# Digital_Port_L_Button.net
KiCad netlist of a schematic drawn in Altium Designer
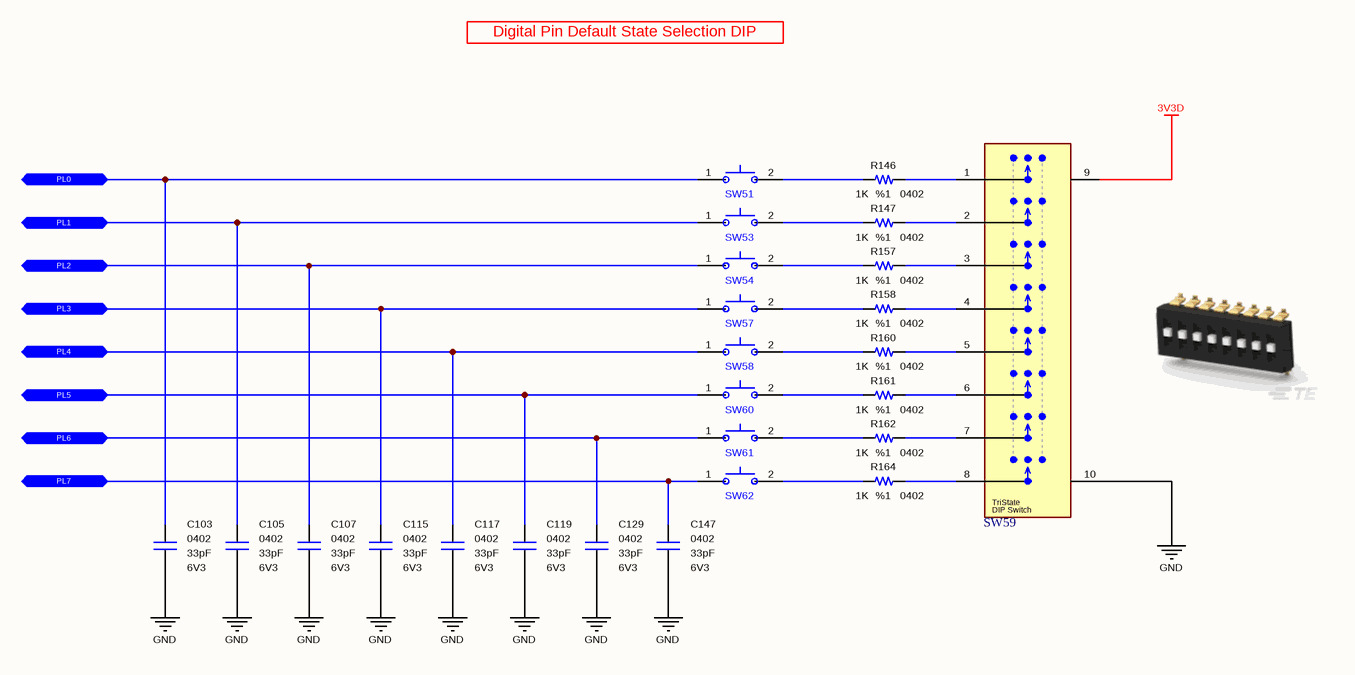
[diagram p0: Digital Port L Button.SchDoc]

(export (version "E")
  (design (tool "Eeschema 10.0.6"))
  (components
    (comp (ref "C103")
      (value "33pF")
      (footprint "CAPACITOR_0402")
      (description "Capacitor - 33pF [0402] (Ceramic)")
      (fields
        (field (name "MANUFACTURER PART NUMBER") "C0402C330J9RACAUTO")
        (field (name "MOUSER PART NUMBER") "80-C0402C330J9RAUTO")
        (field (name "CASE") "0402")
        (field (name "VOLTAGE") "6V3")
      )
      (libsource (lib "Ovoo_Library") (part "Capacitor - 33pF [0402-6V3]"))
    )
    (comp (ref "C105")
      (value "33pF")
      (footprint "CAPACITOR_0402")
      (description "Capacitor - 33pF [0402] (Ceramic)")
      (fields
        (field (name "MANUFACTURER PART NUMBER") "C0402C330J9RACAUTO")
        (field (name "MOUSER PART NUMBER") "80-C0402C330J9RAUTO")
        (field (name "CASE") "0402")
        (field (name "VOLTAGE") "6V3")
      )
      (libsource (lib "Ovoo_Library") (part "Capacitor - 33pF [0402-6V3]"))
    )
    (comp (ref "C107")
      (value "33pF")
      (footprint "CAPACITOR_0402")
      (description "Capacitor - 33pF [0402] (Ceramic)")
      (fields
        (field (name "MANUFACTURER PART NUMBER") "C0402C330J9RACAUTO")
        (field (name "MOUSER PART NUMBER") "80-C0402C330J9RAUTO")
        (field (name "CASE") "0402")
        (field (name "VOLTAGE") "6V3")
      )
      (libsource (lib "Ovoo_Library") (part "Capacitor - 33pF [0402-6V3]"))
    )
    (comp (ref "C115")
      (value "33pF")
      (footprint "CAPACITOR_0402")
      (description "Capacitor - 33pF [0402] (Ceramic)")
      (fields
        (field (name "MANUFACTURER PART NUMBER") "C0402C330J9RACAUTO")
        (field (name "MOUSER PART NUMBER") "80-C0402C330J9RAUTO")
        (field (name "CASE") "0402")
        (field (name "VOLTAGE") "6V3")
      )
      (libsource (lib "Ovoo_Library") (part "Capacitor - 33pF [0402-6V3]"))
    )
    (comp (ref "C117")
      (value "33pF")
      (footprint "CAPACITOR_0402")
      (description "Capacitor - 33pF [0402] (Ceramic)")
      (fields
        (field (name "MANUFACTURER PART NUMBER") "C0402C330J9RACAUTO")
        (field (name "MOUSER PART NUMBER") "80-C0402C330J9RAUTO")
        (field (name "CASE") "0402")
        (field (name "VOLTAGE") "6V3")
      )
      (libsource (lib "Ovoo_Library") (part "Capacitor - 33pF [0402-6V3]"))
    )
    (comp (ref "C119")
      (value "33pF")
      (footprint "CAPACITOR_0402")
      (description "Capacitor - 33pF [0402] (Ceramic)")
      (fields
        (field (name "MANUFACTURER PART NUMBER") "C0402C330J9RACAUTO")
        (field (name "MOUSER PART NUMBER") "80-C0402C330J9RAUTO")
        (field (name "CASE") "0402")
        (field (name "VOLTAGE") "6V3")
      )
      (libsource (lib "Ovoo_Library") (part "Capacitor - 33pF [0402-6V3]"))
    )
    (comp (ref "C129")
      (value "33pF")
      (footprint "CAPACITOR_0402")
      (description "Capacitor - 33pF [0402] (Ceramic)")
      (fields
        (field (name "MANUFACTURER PART NUMBER") "C0402C330J9RACAUTO")
        (field (name "MOUSER PART NUMBER") "80-C0402C330J9RAUTO")
        (field (name "CASE") "0402")
        (field (name "VOLTAGE") "6V3")
      )
      (libsource (lib "Ovoo_Library") (part "Capacitor - 33pF [0402-6V3]"))
    )
    (comp (ref "C147")
      (value "33pF")
      (footprint "CAPACITOR_0402")
      (description "Capacitor - 33pF [0402] (Ceramic)")
      (fields
        (field (name "MANUFACTURER PART NUMBER") "C0402C330J9RACAUTO")
        (field (name "MOUSER PART NUMBER") "80-C0402C330J9RAUTO")
        (field (name "CASE") "0402")
        (field (name "VOLTAGE") "6V3")
      )
      (libsource (lib "Ovoo_Library") (part "Capacitor - 33pF [0402-6V3]"))
    )
    (comp (ref "R146")
      (value "1K")
      (footprint "RESISTOR_0402")
      (description "Thick Film Resistors - SMD 1/16 W 1.0 Kohms 1%")
      (fields
        (field (name "MANUFACTURER PART NUMBER") "CRCW04021K00FKED")
        (field (name "MOUSER PART NUMBER") "71-CRCW0402-1.0K-E3")
        (field (name "TOLERANCE") "%1")
        (field (name "CASE") "0402")
      )
      (libsource (lib "Ovoo_Library") (part "Resistor - 1K"))
    )
    (comp (ref "R147")
      (value "1K")
      (footprint "RESISTOR_0402")
      (description "Thick Film Resistors - SMD 1/16 W 1.0 Kohms 1%")
      (fields
        (field (name "MANUFACTURER PART NUMBER") "CRCW04021K00FKED")
        (field (name "MOUSER PART NUMBER") "71-CRCW0402-1.0K-E3")
        (field (name "TOLERANCE") "%1")
        (field (name "CASE") "0402")
      )
      (libsource (lib "Ovoo_Library") (part "Resistor - 1K"))
    )
    (comp (ref "R157")
      (value "1K")
      (footprint "RESISTOR_0402")
      (description "Thick Film Resistors - SMD 1/16 W 1.0 Kohms 1%")
      (fields
        (field (name "MANUFACTURER PART NUMBER") "CRCW04021K00FKED")
        (field (name "MOUSER PART NUMBER") "71-CRCW0402-1.0K-E3")
        (field (name "TOLERANCE") "%1")
        (field (name "CASE") "0402")
      )
      (libsource (lib "Ovoo_Library") (part "Resistor - 1K"))
    )
    (comp (ref "R158")
      (value "1K")
      (footprint "RESISTOR_0402")
      (description "Thick Film Resistors - SMD 1/16 W 1.0 Kohms 1%")
      (fields
        (field (name "MANUFACTURER PART NUMBER") "CRCW04021K00FKED")
        (field (name "MOUSER PART NUMBER") "71-CRCW0402-1.0K-E3")
        (field (name "TOLERANCE") "%1")
        (field (name "CASE") "0402")
      )
      (libsource (lib "Ovoo_Library") (part "Resistor - 1K"))
    )
    (comp (ref "R160")
      (value "1K")
      (footprint "RESISTOR_0402")
      (description "Thick Film Resistors - SMD 1/16 W 1.0 Kohms 1%")
      (fields
        (field (name "MANUFACTURER PART NUMBER") "CRCW04021K00FKED")
        (field (name "MOUSER PART NUMBER") "71-CRCW0402-1.0K-E3")
        (field (name "TOLERANCE") "%1")
        (field (name "CASE") "0402")
      )
      (libsource (lib "Ovoo_Library") (part "Resistor - 1K"))
    )
    (comp (ref "R161")
      (value "1K")
      (footprint "RESISTOR_0402")
      (description "Thick Film Resistors - SMD 1/16 W 1.0 Kohms 1%")
      (fields
        (field (name "MANUFACTURER PART NUMBER") "CRCW04021K00FKED")
        (field (name "MOUSER PART NUMBER") "71-CRCW0402-1.0K-E3")
        (field (name "TOLERANCE") "%1")
        (field (name "CASE") "0402")
      )
      (libsource (lib "Ovoo_Library") (part "Resistor - 1K"))
    )
    (comp (ref "R162")
      (value "1K")
      (footprint "RESISTOR_0402")
      (description "Thick Film Resistors - SMD 1/16 W 1.0 Kohms 1%")
      (fields
        (field (name "MANUFACTURER PART NUMBER") "CRCW04021K00FKED")
        (field (name "MOUSER PART NUMBER") "71-CRCW0402-1.0K-E3")
        (field (name "TOLERANCE") "%1")
        (field (name "CASE") "0402")
      )
      (libsource (lib "Ovoo_Library") (part "Resistor - 1K"))
    )
    (comp (ref "R164")
      (value "1K")
      (footprint "RESISTOR_0402")
      (description "Thick Film Resistors - SMD 1/16 W 1.0 Kohms 1%")
      (fields
        (field (name "MANUFACTURER PART NUMBER") "CRCW04021K00FKED")
        (field (name "MOUSER PART NUMBER") "71-CRCW0402-1.0K-E3")
        (field (name "TOLERANCE") "%1")
        (field (name "CASE") "0402")
      )
      (libsource (lib "Ovoo_Library") (part "Resistor - 1K"))
    )
    (comp (ref "SW51")
      (value "Tactile Switches")
      (footprint "PTS526_Switch")
      (description "Tactile Switches 50mA 12VDC, 5.2x5.2mm, 0.8mm H, 260gf, G leads.")
      (fields
        (field (name "MANUFACTURER PART NUMBER") "PTS526 SK08 SMTR2 LFS")
        (field (name "MOUSER PART NUMBER") "611-PTS526SK08SMTR2L")
      )
      (libsource (lib "Ovoo_Library") (part "Switch - Tactile"))
    )
    (comp (ref "SW53")
      (value "Tactile Switches")
      (footprint "PTS526_Switch")
      (description "Tactile Switches 50mA 12VDC, 5.2x5.2mm, 0.8mm H, 260gf, G leads.")
      (fields
        (field (name "MANUFACTURER PART NUMBER") "PTS526 SK08 SMTR2 LFS")
        (field (name "MOUSER PART NUMBER") "611-PTS526SK08SMTR2L")
      )
      (libsource (lib "Ovoo_Library") (part "Switch - Tactile"))
    )
    (comp (ref "SW54")
      (value "Tactile Switches")
      (footprint "PTS526_Switch")
      (description "Tactile Switches 50mA 12VDC, 5.2x5.2mm, 0.8mm H, 260gf, G leads.")
      (fields
        (field (name "MANUFACTURER PART NUMBER") "PTS526 SK08 SMTR2 LFS")
        (field (name "MOUSER PART NUMBER") "611-PTS526SK08SMTR2L")
      )
      (libsource (lib "Ovoo_Library") (part "Switch - Tactile"))
    )
    (comp (ref "SW57")
      (value "Tactile Switches")
      (footprint "PTS526_Switch")
      (description "Tactile Switches 50mA 12VDC, 5.2x5.2mm, 0.8mm H, 260gf, G leads.")
      (fields
        (field (name "MANUFACTURER PART NUMBER") "PTS526 SK08 SMTR2 LFS")
        (field (name "MOUSER PART NUMBER") "611-PTS526SK08SMTR2L")
      )
      (libsource (lib "Ovoo_Library") (part "Switch - Tactile"))
    )
    (comp (ref "SW58")
      (value "Tactile Switches")
      (footprint "PTS526_Switch")
      (description "Tactile Switches 50mA 12VDC, 5.2x5.2mm, 0.8mm H, 260gf, G leads.")
      (fields
        (field (name "MANUFACTURER PART NUMBER") "PTS526 SK08 SMTR2 LFS")
        (field (name "MOUSER PART NUMBER") "611-PTS526SK08SMTR2L")
      )
      (libsource (lib "Ovoo_Library") (part "Switch - Tactile"))
    )
    (comp (ref "SW59")
      (value "DIP Switches/SIP Switches")
      (footprint "TDS08SGNNTR04")
      (description "DIP Switches/SIP Switches TRI-STATE DIP 8P G RAISED T&R")
      (fields
        (field (name "MANUFACTURER PART NUMBER") "TDS08SGNNTR04")
        (field (name "MOUSER PART NUMBER") "506-TDS08SGNNTR04")
      )
      (libsource (lib "Ovoo_Library") (part "Switch - DIP Switch (8 Pole TriState)"))
    )
    (comp (ref "SW60")
      (value "Tactile Switches")
      (footprint "PTS526_Switch")
      (description "Tactile Switches 50mA 12VDC, 5.2x5.2mm, 0.8mm H, 260gf, G leads.")
      (fields
        (field (name "MANUFACTURER PART NUMBER") "PTS526 SK08 SMTR2 LFS")
        (field (name "MOUSER PART NUMBER") "611-PTS526SK08SMTR2L")
      )
      (libsource (lib "Ovoo_Library") (part "Switch - Tactile"))
    )
    (comp (ref "SW61")
      (value "Tactile Switches")
      (footprint "PTS526_Switch")
      (description "Tactile Switches 50mA 12VDC, 5.2x5.2mm, 0.8mm H, 260gf, G leads.")
      (fields
        (field (name "MANUFACTURER PART NUMBER") "PTS526 SK08 SMTR2 LFS")
        (field (name "MOUSER PART NUMBER") "611-PTS526SK08SMTR2L")
      )
      (libsource (lib "Ovoo_Library") (part "Switch - Tactile"))
    )
    (comp (ref "SW62")
      (value "Tactile Switches")
      (footprint "PTS526_Switch")
      (description "Tactile Switches 50mA 12VDC, 5.2x5.2mm, 0.8mm H, 260gf, G leads.")
      (fields
        (field (name "MANUFACTURER PART NUMBER") "PTS526 SK08 SMTR2 LFS")
        (field (name "MOUSER PART NUMBER") "611-PTS526SK08SMTR2L")
      )
      (libsource (lib "Ovoo_Library") (part "Switch - Tactile"))
    )
  )
  (nets
    (net (code "1") (name "/PL0") (class "Default")
      (node (ref "C103") (pin "2") (pinfunction "2_2") (pintype "passive"))
      (node (ref "SW51") (pin "1") (pinfunction "NC_1") (pintype "passive"))
    )
    (net (code "2") (name "/PL1") (class "Default")
      (node (ref "C105") (pin "2") (pinfunction "2_2") (pintype "passive"))
      (node (ref "SW53") (pin "1") (pinfunction "NC_1") (pintype "passive"))
    )
    (net (code "3") (name "/PL2") (class "Default")
      (node (ref "C107") (pin "2") (pinfunction "2_2") (pintype "passive"))
      (node (ref "SW54") (pin "1") (pinfunction "NC_1") (pintype "passive"))
    )
    (net (code "4") (name "/PL3") (class "Default")
      (node (ref "C115") (pin "2") (pinfunction "2_2") (pintype "passive"))
      (node (ref "SW57") (pin "1") (pinfunction "NC_1") (pintype "passive"))
    )
    (net (code "5") (name "/PL4") (class "Default")
      (node (ref "C117") (pin "2") (pinfunction "2_2") (pintype "passive"))
      (node (ref "SW58") (pin "1") (pinfunction "NC_1") (pintype "passive"))
    )
    (net (code "6") (name "/PL5") (class "Default")
      (node (ref "C119") (pin "2") (pinfunction "2_2") (pintype "passive"))
      (node (ref "SW60") (pin "1") (pinfunction "NC_1") (pintype "passive"))
    )
    (net (code "7") (name "/PL6") (class "Default")
      (node (ref "C129") (pin "2") (pinfunction "2_2") (pintype "passive"))
      (node (ref "SW61") (pin "1") (pinfunction "NC_1") (pintype "passive"))
    )
    (net (code "8") (name "/PL7") (class "Default")
      (node (ref "C147") (pin "2") (pinfunction "2_2") (pintype "passive"))
      (node (ref "SW62") (pin "1") (pinfunction "NC_1") (pintype "passive"))
    )
    (net (code "9") (name "3V3D") (class "Default")
      (node (ref "SW59") (pin "9") (pinfunction "VCC_9") (pintype "passive"))
    )
    (net (code "10") (name "GND") (class "Default")
      (node (ref "C103") (pin "1") (pinfunction "1_1") (pintype "passive"))
      (node (ref "C105") (pin "1") (pinfunction "1_1") (pintype "passive"))
      (node (ref "C107") (pin "1") (pinfunction "1_1") (pintype "passive"))
      (node (ref "C115") (pin "1") (pinfunction "1_1") (pintype "passive"))
      (node (ref "C117") (pin "1") (pinfunction "1_1") (pintype "passive"))
      (node (ref "C119") (pin "1") (pinfunction "1_1") (pintype "passive"))
      (node (ref "C129") (pin "1") (pinfunction "1_1") (pintype "passive"))
      (node (ref "C147") (pin "1") (pinfunction "1_1") (pintype "passive"))
      (node (ref "SW59") (pin "10") (pinfunction "GND_10") (pintype "passive"))
    )
    (net (code "11") (name "Net-(R146-Pad1)") (class "Default")
      (node (ref "R146") (pin "1") (pinfunction "1_1") (pintype "passive"))
      (node (ref "SW59") (pin "1") (pinfunction "1_1") (pintype "passive"))
    )
    (net (code "12") (name "Net-(R147-Pad1)") (class "Default")
      (node (ref "R147") (pin "1") (pinfunction "1_1") (pintype "passive"))
      (node (ref "SW59") (pin "2") (pinfunction "2_2") (pintype "passive"))
    )
    (net (code "13") (name "Net-(R157-Pad1)") (class "Default")
      (node (ref "R157") (pin "1") (pinfunction "1_1") (pintype "passive"))
      (node (ref "SW59") (pin "3") (pinfunction "3_3") (pintype "passive"))
    )
    (net (code "14") (name "Net-(R158-Pad1)") (class "Default")
      (node (ref "R158") (pin "1") (pinfunction "1_1") (pintype "passive"))
      (node (ref "SW59") (pin "4") (pinfunction "4_4") (pintype "passive"))
    )
    (net (code "15") (name "Net-(R160-Pad1)") (class "Default")
      (node (ref "R160") (pin "1") (pinfunction "1_1") (pintype "passive"))
      (node (ref "SW59") (pin "5") (pinfunction "5_5") (pintype "passive"))
    )
    (net (code "16") (name "Net-(R161-Pad1)") (class "Default")
      (node (ref "R161") (pin "1") (pinfunction "1_1") (pintype "passive"))
      (node (ref "SW59") (pin "6") (pinfunction "6_6") (pintype "passive"))
    )
    (net (code "17") (name "Net-(R162-Pad1)") (class "Default")
      (node (ref "R162") (pin "1") (pinfunction "1_1") (pintype "passive"))
      (node (ref "SW59") (pin "7") (pinfunction "7_7") (pintype "passive"))
    )
    (net (code "18") (name "Net-(R164-Pad1)") (class "Default")
      (node (ref "R164") (pin "1") (pinfunction "1_1") (pintype "passive"))
      (node (ref "SW59") (pin "8") (pinfunction "8_8") (pintype "passive"))
    )
    (net (code "19") (name "Net-(SW51-COM)") (class "Default")
      (node (ref "R146") (pin "2") (pinfunction "2_2") (pintype "passive"))
      (node (ref "SW51") (pin "2") (pinfunction "COM_2") (pintype "passive"))
    )
    (net (code "20") (name "Net-(SW53-COM)") (class "Default")
      (node (ref "R147") (pin "2") (pinfunction "2_2") (pintype "passive"))
      (node (ref "SW53") (pin "2") (pinfunction "COM_2") (pintype "passive"))
    )
    (net (code "21") (name "Net-(SW54-COM)") (class "Default")
      (node (ref "R157") (pin "2") (pinfunction "2_2") (pintype "passive"))
      (node (ref "SW54") (pin "2") (pinfunction "COM_2") (pintype "passive"))
    )
    (net (code "22") (name "Net-(SW57-COM)") (class "Default")
      (node (ref "R158") (pin "2") (pinfunction "2_2") (pintype "passive"))
      (node (ref "SW57") (pin "2") (pinfunction "COM_2") (pintype "passive"))
    )
    (net (code "23") (name "Net-(SW58-COM)") (class "Default")
      (node (ref "R160") (pin "2") (pinfunction "2_2") (pintype "passive"))
      (node (ref "SW58") (pin "2") (pinfunction "COM_2") (pintype "passive"))
    )
    (net (code "24") (name "Net-(SW60-COM)") (class "Default")
      (node (ref "R161") (pin "2") (pinfunction "2_2") (pintype "passive"))
      (node (ref "SW60") (pin "2") (pinfunction "COM_2") (pintype "passive"))
    )
    (net (code "25") (name "Net-(SW61-COM)") (class "Default")
      (node (ref "R162") (pin "2") (pinfunction "2_2") (pintype "passive"))
      (node (ref "SW61") (pin "2") (pinfunction "COM_2") (pintype "passive"))
    )
    (net (code "26") (name "Net-(SW62-COM)") (class "Default")
      (node (ref "R164") (pin "2") (pinfunction "2_2") (pintype "passive"))
      (node (ref "SW62") (pin "2") (pinfunction "COM_2") (pintype "passive"))
    )
  )
)
